# Board_Nano.net
KiCad netlist of a schematic drawn in EAGLE
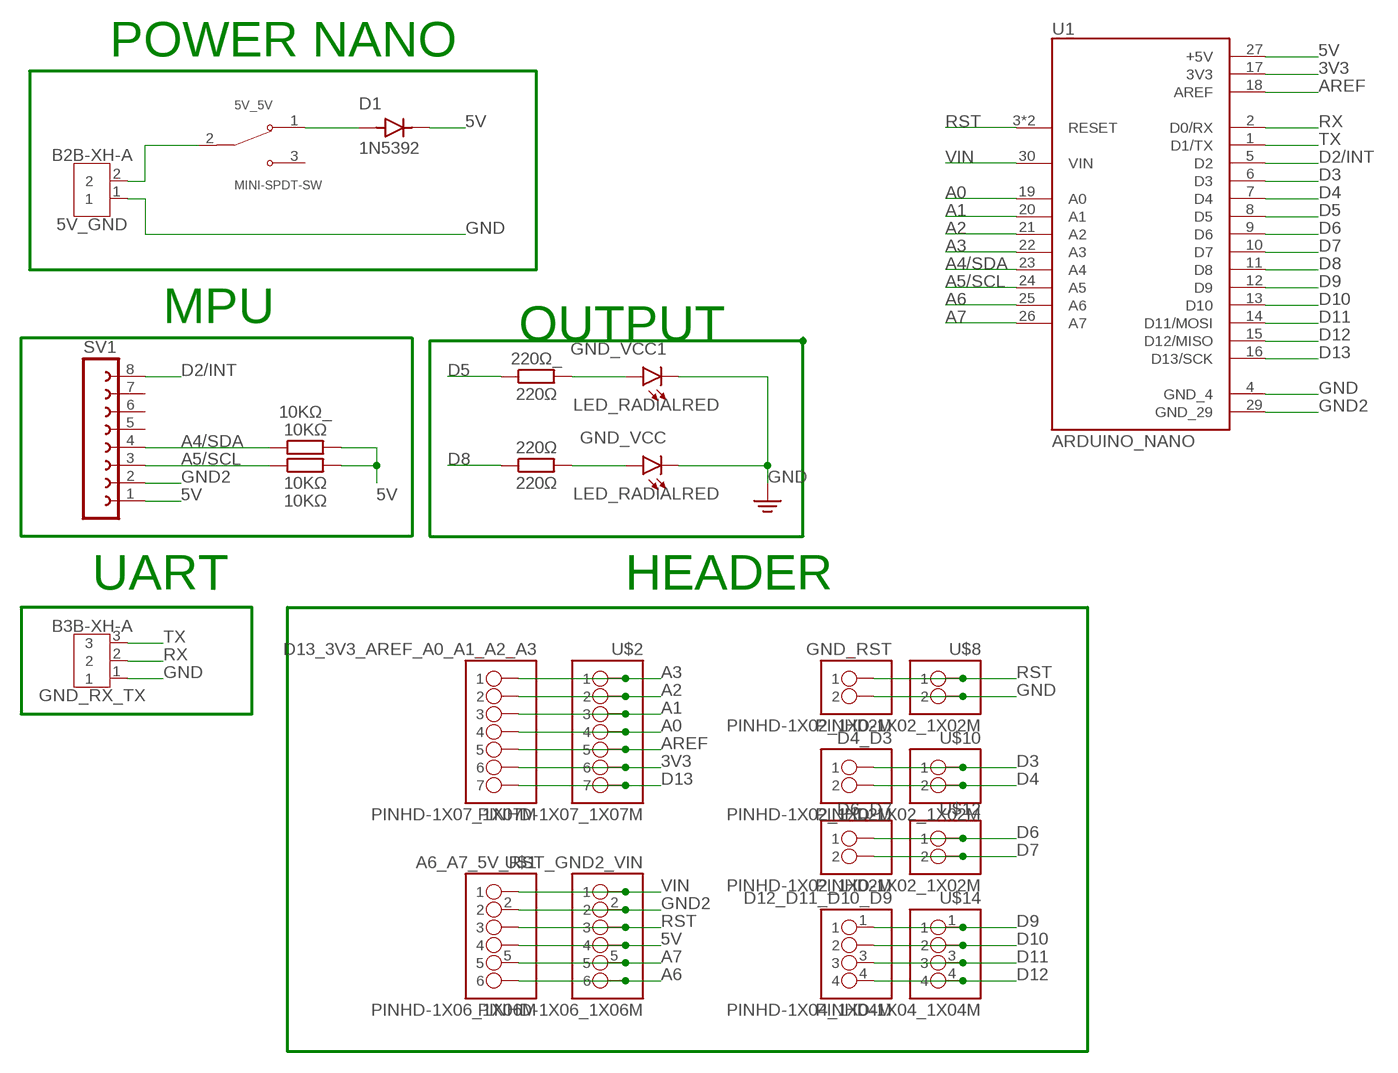
[diagram p0: schematic, sheet 1]

(export (version "E")
  (design (tool "Eeschema 10.0.6"))
  (components
    (comp (ref "5V_5V")
      (value "MINI-SPDT-SW")
      (footprint "eagle-import:SW_MINI-SPDT-SW")
      (fields (field (name "MF") "Gravitech"))
      (libsource (lib "eagle-import") (part "MINI-SPDT-SW"))
    )
    (comp (ref "5V_GND")
      (value "B2B-XH-A")
      (footprint "eagle-import:B2B-XH-A")
      (fields (field (name "MANUFACTURER") "JST Sales America Inc."))
      (libsource (lib "eagle-import") (part "B2B-XH-A"))
    )
    (comp (ref "10KΩ")
      (value "10KΩ")
      (footprint "eagle-import:RESAD1176W63L850D250B")
      (libsource (lib "eagle-import") (part "RAXIAL-11.7MM-PITCH_"))
    )
    (comp (ref "10KΩ_")
      (value "10KΩ")
      (footprint "eagle-import:RESAD1176W63L850D250B")
      (libsource (lib "eagle-import") (part "RAXIAL-11.7MM-PITCH_"))
    )
    (comp (ref "220Ω")
      (value "220Ω")
      (footprint "eagle-import:RESAD1176W63L850D250B")
      (libsource (lib "eagle-import") (part "RAXIAL-11.7MM-PITCH_"))
    )
    (comp (ref "220Ω_")
      (value "220Ω")
      (footprint "eagle-import:RESAD1176W63L850D250B")
      (libsource (lib "eagle-import") (part "RAXIAL-11.7MM-PITCH_"))
    )
    (comp (ref "A6_A7_5V_RST_GND2_VIN")
      (value "PINHD-1X06_1X06M")
      (footprint "eagle-import:1X06")
      (libsource (lib "eagle-import") (part "PINHD-1X06_1X06M"))
    )
    (comp (ref "D1")
      (value "1N5392")
      (footprint "eagle-import:DIOAD1300W80L670D310")
      (fields (field (name "MF") "ON Semiconductor"))
      (libsource (lib "eagle-import") (part "1N5392"))
    )
    (comp (ref "D4_D3")
      (value "PINHD-1X02_1X02M")
      (footprint "eagle-import:1X02")
      (libsource (lib "eagle-import") (part "PINHD-1X02_1X02M"))
    )
    (comp (ref "D6_D7")
      (value "PINHD-1X02_1X02M")
      (footprint "eagle-import:1X02")
      (libsource (lib "eagle-import") (part "PINHD-1X02_1X02M"))
    )
    (comp (ref "D12_D11_D10_D9")
      (value "PINHD-1X04_1X04M")
      (footprint "eagle-import:1X04")
      (libsource (lib "eagle-import") (part "PINHD-1X04_1X04M"))
    )
    (comp (ref "D13_3V3_AREF_A0_A1_A2_A3")
      (value "PINHD-1X07_1X07M")
      (footprint "eagle-import:1X07")
      (libsource (lib "eagle-import") (part "PINHD-1X07_1X07M"))
    )
    (comp (ref "GND_RST")
      (value "PINHD-1X02_1X02M")
      (footprint "eagle-import:1X02")
      (libsource (lib "eagle-import") (part "PINHD-1X02_1X02M"))
    )
    (comp (ref "GND_RX_TX")
      (value "B3B-XH-A")
      (footprint "eagle-import:B3B-XH-A")
      (fields (field (name "MANUFACTURER") "JST Sales America Inc."))
      (libsource (lib "eagle-import") (part "B3B-XH-A"))
    )
    (comp (ref "GND_VCC")
      (value "LED_RADIALRED")
      (footprint "eagle-import:LEDRD254W60D565H860B_R")
      (libsource (lib "eagle-import") (part "LED_RADIALRED"))
    )
    (comp (ref "GND_VCC1")
      (value "LED_RADIALRED")
      (footprint "eagle-import:LEDRD254W60D565H860B_R")
      (libsource (lib "eagle-import") (part "LED_RADIALRED"))
    )
    (comp (ref "SV1")
      (value "FE08-1")
      (footprint "eagle-import:FE08")
      (libsource (lib "eagle-import") (part "FE08-1"))
    )
    (comp (ref "U$1")
      (value "PINHD-1X06_1X06M")
      (footprint "eagle-import:1X06")
      (libsource (lib "eagle-import") (part "PINHD-1X06_1X06M"))
    )
    (comp (ref "U$2")
      (value "PINHD-1X07_1X07M")
      (footprint "eagle-import:1X07")
      (libsource (lib "eagle-import") (part "PINHD-1X07_1X07M"))
    )
    (comp (ref "U$8")
      (value "PINHD-1X02_1X02M")
      (footprint "eagle-import:1X02")
      (libsource (lib "eagle-import") (part "PINHD-1X02_1X02M"))
    )
    (comp (ref "U$10")
      (value "PINHD-1X02_1X02M")
      (footprint "eagle-import:1X02")
      (libsource (lib "eagle-import") (part "PINHD-1X02_1X02M"))
    )
    (comp (ref "U$12")
      (value "PINHD-1X02_1X02M")
      (footprint "eagle-import:1X02")
      (libsource (lib "eagle-import") (part "PINHD-1X02_1X02M"))
    )
    (comp (ref "U$14")
      (value "PINHD-1X04_1X04M")
      (footprint "eagle-import:1X04")
      (libsource (lib "eagle-import") (part "PINHD-1X04_1X04M"))
    )
    (comp (ref "U1")
      (value "ARDUINO_NANO")
      (footprint "eagle-import:MODULE_ARDUINO_NANO")
      (fields (field (name "MF") "Arduino") (field (name "MP") "Arduino Nano"))
      (libsource (lib "eagle-import") (part "ARDUINO_NANO"))
    )
  )
  (nets
    (net (code "1") (name "/3V3") (class "Default")
      (node (ref "D13_3V3_AREF_A0_A1_A2_A3") (pin "6") (pinfunction "6_6") (pintype "bidirectional"))
      (node (ref "U$2") (pin "6") (pinfunction "6_6") (pintype "bidirectional"))
      (node (ref "U1") (pin "17") (pinfunction "3V3_17") (pintype "power_in"))
    )
    (net (code "2") (name "/5V") (class "Default")
      (node (ref "10KΩ") (pin "2") (pinfunction "2_2") (pintype "passive"))
      (node (ref "10KΩ_") (pin "2") (pinfunction "2_2") (pintype "passive"))
      (node (ref "A6_A7_5V_RST_GND2_VIN") (pin "4") (pinfunction "4_4") (pintype "bidirectional"))
      (node (ref "D1") (pin "C") (pinfunction "K_C") (pintype "passive"))
      (node (ref "SV1") (pin "1") (pinfunction "1_1") (pintype "passive"))
      (node (ref "U$1") (pin "4") (pinfunction "4_4") (pintype "bidirectional"))
      (node (ref "U1") (pin "27") (pinfunction "+5V_27") (pintype "power_in"))
    )
    (net (code "3") (name "/A0") (class "Default")
      (node (ref "D13_3V3_AREF_A0_A1_A2_A3") (pin "4") (pinfunction "4_4") (pintype "bidirectional"))
      (node (ref "U$2") (pin "4") (pinfunction "4_4") (pintype "bidirectional"))
      (node (ref "U1") (pin "19") (pinfunction "A0_19") (pintype "input"))
    )
    (net (code "4") (name "/A1") (class "Default")
      (node (ref "D13_3V3_AREF_A0_A1_A2_A3") (pin "3") (pinfunction "3_3") (pintype "bidirectional"))
      (node (ref "U$2") (pin "3") (pinfunction "3_3") (pintype "bidirectional"))
      (node (ref "U1") (pin "20") (pinfunction "A1_20") (pintype "input"))
    )
    (net (code "5") (name "/A2") (class "Default")
      (node (ref "D13_3V3_AREF_A0_A1_A2_A3") (pin "2") (pinfunction "2_2") (pintype "bidirectional"))
      (node (ref "U$2") (pin "2") (pinfunction "2_2") (pintype "bidirectional"))
      (node (ref "U1") (pin "21") (pinfunction "A2_21") (pintype "input"))
    )
    (net (code "6") (name "/A3") (class "Default")
      (node (ref "D13_3V3_AREF_A0_A1_A2_A3") (pin "1") (pinfunction "1_1") (pintype "bidirectional"))
      (node (ref "U$2") (pin "1") (pinfunction "1_1") (pintype "bidirectional"))
      (node (ref "U1") (pin "22") (pinfunction "A3_22") (pintype "input"))
    )
    (net (code "7") (name "/A4{slash}SDA") (class "Default")
      (node (ref "10KΩ_") (pin "1") (pinfunction "1_1") (pintype "passive"))
      (node (ref "SV1") (pin "4") (pinfunction "4_4") (pintype "passive"))
      (node (ref "U1") (pin "23") (pinfunction "A4_23") (pintype "input"))
    )
    (net (code "8") (name "/A5{slash}SCL") (class "Default")
      (node (ref "10KΩ") (pin "1") (pinfunction "1_1") (pintype "passive"))
      (node (ref "SV1") (pin "3") (pinfunction "3_3") (pintype "passive"))
      (node (ref "U1") (pin "24") (pinfunction "A5_24") (pintype "input"))
    )
    (net (code "9") (name "/A6") (class "Default")
      (node (ref "A6_A7_5V_RST_GND2_VIN") (pin "6") (pinfunction "6_6") (pintype "bidirectional"))
      (node (ref "U$1") (pin "6") (pinfunction "6_6") (pintype "bidirectional"))
      (node (ref "U1") (pin "25") (pinfunction "A6_25") (pintype "input"))
    )
    (net (code "10") (name "/A7") (class "Default")
      (node (ref "A6_A7_5V_RST_GND2_VIN") (pin "5") (pinfunction "5_5") (pintype "bidirectional"))
      (node (ref "U$1") (pin "5") (pinfunction "5_5") (pintype "bidirectional"))
      (node (ref "U1") (pin "26") (pinfunction "A7_26") (pintype "input"))
    )
    (net (code "11") (name "/AREF") (class "Default")
      (node (ref "D13_3V3_AREF_A0_A1_A2_A3") (pin "5") (pinfunction "5_5") (pintype "bidirectional"))
      (node (ref "U$2") (pin "5") (pinfunction "5_5") (pintype "bidirectional"))
      (node (ref "U1") (pin "18") (pinfunction "AREF_18") (pintype "power_in"))
    )
    (net (code "12") (name "/D2{slash}INT") (class "Default")
      (node (ref "SV1") (pin "8") (pinfunction "8_8") (pintype "passive"))
      (node (ref "U1") (pin "5") (pinfunction "D2_5") (pintype "bidirectional"))
    )
    (net (code "13") (name "/D3") (class "Default")
      (node (ref "D4_D3") (pin "1") (pinfunction "1_1") (pintype "bidirectional"))
      (node (ref "U$10") (pin "1") (pinfunction "1_1") (pintype "bidirectional"))
      (node (ref "U1") (pin "6") (pinfunction "D3_6") (pintype "bidirectional"))
    )
    (net (code "14") (name "/D4") (class "Default")
      (node (ref "D4_D3") (pin "2") (pinfunction "2_2") (pintype "bidirectional"))
      (node (ref "U$10") (pin "2") (pinfunction "2_2") (pintype "bidirectional"))
      (node (ref "U1") (pin "7") (pinfunction "D4_7") (pintype "bidirectional"))
    )
    (net (code "15") (name "/D5") (class "Default")
      (node (ref "220Ω_") (pin "1") (pinfunction "1_1") (pintype "passive"))
      (node (ref "U1") (pin "8") (pinfunction "D5_8") (pintype "bidirectional"))
    )
    (net (code "16") (name "/D6") (class "Default")
      (node (ref "D6_D7") (pin "1") (pinfunction "1_1") (pintype "bidirectional"))
      (node (ref "U$12") (pin "1") (pinfunction "1_1") (pintype "bidirectional"))
      (node (ref "U1") (pin "9") (pinfunction "D6_9") (pintype "bidirectional"))
    )
    (net (code "17") (name "/D7") (class "Default")
      (node (ref "D6_D7") (pin "2") (pinfunction "2_2") (pintype "bidirectional"))
      (node (ref "U$12") (pin "2") (pinfunction "2_2") (pintype "bidirectional"))
      (node (ref "U1") (pin "10") (pinfunction "D7_10") (pintype "bidirectional"))
    )
    (net (code "18") (name "/D8") (class "Default")
      (node (ref "220Ω") (pin "1") (pinfunction "1_1") (pintype "passive"))
      (node (ref "U1") (pin "11") (pinfunction "D8_11") (pintype "bidirectional"))
    )
    (net (code "19") (name "/D9") (class "Default")
      (node (ref "D12_D11_D10_D9") (pin "1") (pinfunction "1_1") (pintype "bidirectional"))
      (node (ref "U$14") (pin "1") (pinfunction "1_1") (pintype "bidirectional"))
      (node (ref "U1") (pin "12") (pinfunction "D9_12") (pintype "bidirectional"))
    )
    (net (code "20") (name "/D10") (class "Default")
      (node (ref "D12_D11_D10_D9") (pin "2") (pinfunction "2_2") (pintype "bidirectional"))
      (node (ref "U$14") (pin "2") (pinfunction "2_2") (pintype "bidirectional"))
      (node (ref "U1") (pin "13") (pinfunction "D10_13") (pintype "bidirectional"))
    )
    (net (code "21") (name "/D11") (class "Default")
      (node (ref "D12_D11_D10_D9") (pin "3") (pinfunction "3_3") (pintype "bidirectional"))
      (node (ref "U$14") (pin "3") (pinfunction "3_3") (pintype "bidirectional"))
      (node (ref "U1") (pin "14") (pinfunction "D11/MOSI_14") (pintype "bidirectional"))
    )
    (net (code "22") (name "/D12") (class "Default")
      (node (ref "D12_D11_D10_D9") (pin "4") (pinfunction "4_4") (pintype "bidirectional"))
      (node (ref "U$14") (pin "4") (pinfunction "4_4") (pintype "bidirectional"))
      (node (ref "U1") (pin "15") (pinfunction "D12/MISO_15") (pintype "bidirectional"))
    )
    (net (code "23") (name "/D13") (class "Default")
      (node (ref "D13_3V3_AREF_A0_A1_A2_A3") (pin "7") (pinfunction "7_7") (pintype "bidirectional"))
      (node (ref "U$2") (pin "7") (pinfunction "7_7") (pintype "bidirectional"))
      (node (ref "U1") (pin "16") (pinfunction "D13/SCK_16") (pintype "bidirectional"))
    )
    (net (code "24") (name "/GND2") (class "Default")
      (node (ref "A6_A7_5V_RST_GND2_VIN") (pin "2") (pinfunction "2_2") (pintype "bidirectional"))
      (node (ref "SV1") (pin "2") (pinfunction "2_2") (pintype "passive"))
      (node (ref "U$1") (pin "2") (pinfunction "2_2") (pintype "bidirectional"))
      (node (ref "U1") (pin "29") (pinfunction "GND_29_29") (pintype "power_in"))
    )
    (net (code "25") (name "/RST") (class "Default")
      (node (ref "A6_A7_5V_RST_GND2_VIN") (pin "3") (pinfunction "3_3") (pintype "bidirectional"))
      (node (ref "GND_RST") (pin "1") (pinfunction "1_1") (pintype "bidirectional"))
      (node (ref "U$1") (pin "3") (pinfunction "3_3") (pintype "bidirectional"))
      (node (ref "U$8") (pin "1") (pinfunction "1_1") (pintype "bidirectional"))
      (node (ref "U1") (pin "28") (pinfunction "RESET_28") (pintype "input"))
      (node (ref "U1") (pin "3") (pinfunction "RESET_3") (pintype "input"))
    )
    (net (code "26") (name "/RX") (class "Default")
      (node (ref "GND_RX_TX") (pin "2") (pinfunction "2_2") (pintype "bidirectional"))
      (node (ref "U1") (pin "2") (pinfunction "D0/RX_2") (pintype "bidirectional"))
    )
    (net (code "27") (name "/TX") (class "Default")
      (node (ref "GND_RX_TX") (pin "3") (pinfunction "3_3") (pintype "bidirectional"))
      (node (ref "U1") (pin "1") (pinfunction "D1/TX_1") (pintype "bidirectional"))
    )
    (net (code "28") (name "/VIN") (class "Default")
      (node (ref "A6_A7_5V_RST_GND2_VIN") (pin "1") (pinfunction "1_1") (pintype "bidirectional"))
      (node (ref "U$1") (pin "1") (pinfunction "1_1") (pintype "bidirectional"))
      (node (ref "U1") (pin "30") (pinfunction "VIN_30") (pintype "input"))
    )
    (net (code "29") (name "GND") (class "Default")
      (node (ref "5V_GND") (pin "1") (pinfunction "1_1") (pintype "bidirectional"))
      (node (ref "GND_RST") (pin "2") (pinfunction "2_2") (pintype "bidirectional"))
      (node (ref "GND_RX_TX") (pin "1") (pinfunction "1_1") (pintype "bidirectional"))
      (node (ref "GND_VCC") (pin "C") (pinfunction "C_C") (pintype "passive"))
      (node (ref "GND_VCC1") (pin "C") (pinfunction "C_C") (pintype "passive"))
      (node (ref "U$8") (pin "2") (pinfunction "2_2") (pintype "bidirectional"))
      (node (ref "U1") (pin "4") (pinfunction "GND_4_4") (pintype "power_in"))
    )
    (net (code "30") (name "Net-(5V_5V-Pad1)") (class "Default")
      (node (ref "5V_5V") (pin "1") (pinfunction "1_1") (pintype "passive"))
      (node (ref "D1") (pin "A") (pinfunction "A_A") (pintype "passive"))
    )
    (net (code "31") (name "Net-(5V_5V-Pad2)") (class "Default")
      (node (ref "5V_5V") (pin "2") (pinfunction "2_2") (pintype "passive"))
      (node (ref "5V_GND") (pin "2") (pinfunction "2_2") (pintype "bidirectional"))
    )
    (net (code "32") (name "Net-(220Ω-Pad2)") (class "Default")
      (node (ref "220Ω") (pin "2") (pinfunction "2_2") (pintype "passive"))
      (node (ref "GND_VCC") (pin "A") (pinfunction "A_A") (pintype "passive"))
    )
    (net (code "33") (name "Net-(220Ω_-Pad2)") (class "Default")
      (node (ref "220Ω_") (pin "2") (pinfunction "2_2") (pintype "passive"))
      (node (ref "GND_VCC1") (pin "A") (pinfunction "A_A") (pintype "passive"))
    )
    (net (code "34") (name "unconnected-(5V_5V-Pad3)") (class "Default")
      (node (ref "5V_5V") (pin "3") (pinfunction "3_3") (pintype "passive"))
    )
    (net (code "35") (name "unconnected-(SV1-Pad5)") (class "Default")
      (node (ref "SV1") (pin "5") (pinfunction "5_5") (pintype "passive"))
    )
    (net (code "36") (name "unconnected-(SV1-Pad6)") (class "Default")
      (node (ref "SV1") (pin "6") (pinfunction "6_6") (pintype "passive"))
    )
    (net (code "37") (name "unconnected-(SV1-Pad7)") (class "Default")
      (node (ref "SV1") (pin "7") (pinfunction "7_7") (pintype "passive"))
    )
  )
)
